# sensors.net
KiCad netlist of a schematic drawn in Altium Designer
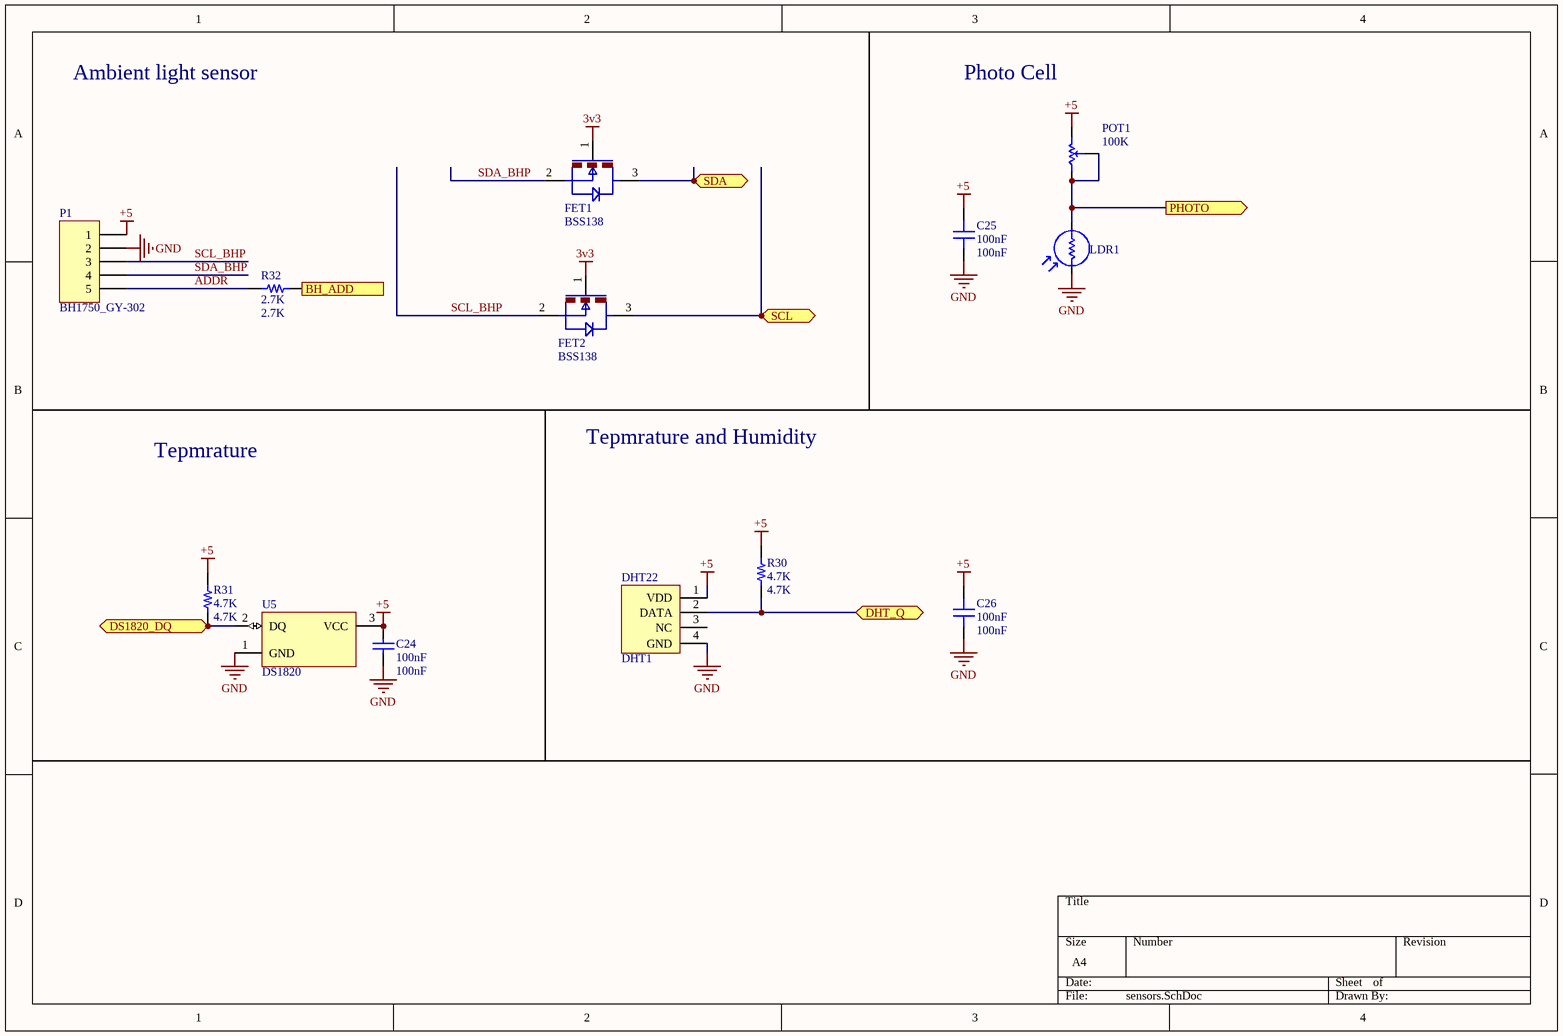
[diagram p0: sensors.SchDoc]

(export (version "E")
  (design (tool "Eeschema 10.0.6"))
  (components
    (comp (ref "C24")
      (value "100nF")
      (footprint "0603C")
      (description "CAP SMD 0603")
      (fields (field (name "ALTIUM_VALUE") "100nF") (field (name "PUBLISHER") "Altium Limited"))
      (libsource (lib "Miscellaneous Devices") (part "Cap"))
    )
    (comp (ref "C25")
      (value "100nF")
      (footprint "0603C")
      (description "CAP SMD 0603")
      (fields (field (name "PART NUMBER") "C0805X106K9RAC7800") (field (name "ALTIUM_VALUE") "100nF"))
      (libsource (lib "lamp control-ver2") (part "Capacitor"))
    )
    (comp (ref "C26")
      (value "100nF")
      (footprint "0603C")
      (description "CAP SMD 0603")
      (fields (field (name "PART NUMBER") "C0805X106K9RAC7800") (field (name "ALTIUM_VALUE") "100nF"))
      (libsource (lib "lamp control-ver2") (part "Capacitor"))
    )
    (comp (ref "DHT1")
      (value "DHT22")
      (footprint "DHT22")
      (description "Temprature & Humidity Sensor")
      (libsource (lib "Altium") (part "DHT22"))
    )
    (comp (ref "FET1")
      (value "BSS138")
      (footprint "SOT-23")
      (description "MOSFET N-channel SMD")
      (libsource (lib "ZetaBoard_Lib") (part "BSS138"))
    )
    (comp (ref "FET2")
      (value "BSS138")
      (footprint "SOT-23")
      (description "MOSFET N-channel SMD")
      (libsource (lib "ZetaBoard_Lib") (part "BSS138"))
    )
    (comp (ref "LDR1")
      (value "PhotoCell-5mm")
      (footprint "PhotoCell")
      (description "Photo Cell- Variable Resistor With Light")
      (fields (field (name "DESIGNER") "Saeid Jorablo"))
      (libsource (lib "Altium") (part "LDR"))
    )
    (comp (ref "P1")
      (value "BH1750_GY-302")
      (footprint "BH1750")
      (description "Ambiant light sensor")
      (fields (field (name "PUBLISHER") "Altium Limited"))
      (libsource (lib "Altium (2)") (part "Header 5"))
    )
    (comp (ref "POT1")
      (value "100K")
      (footprint "POT 2")
      (description "Variable Resistor")
      (libsource (lib "Altium (2)") (part "POT"))
    )
    (comp (ref "R30")
      (value "4.7K")
      (footprint "0603R")
      (description "RES SMD 0603")
      (fields (field (name "PART NUMBER") "RCS0805100KFKEA") (field (name "ALTIUM_VALUE") "4.7K"))
      (libsource (lib "lamp control-ver2") (part "Resistor"))
    )
    (comp (ref "R31")
      (value "4.7K")
      (footprint "0603R")
      (description "RES SMD 0603")
      (fields (field (name "PART NUMBER") "RCS0805100KFKEA") (field (name "ALTIUM_VALUE") "4.7K"))
      (libsource (lib "lamp control-ver2") (part "Resistor"))
    )
    (comp (ref "R32")
      (value "2.7K")
      (footprint "0603R")
      (description "RES SMD 0603")
      (fields (field (name "PART NUMBER") "RCS0805100KFKEA") (field (name "ALTIUM_VALUE") "2.7K"))
      (libsource (lib "lamp control-ver2") (part "Resistor"))
    )
    (comp (ref "U5")
      (value "DS1820")
      (footprint "DS1820")
      (description "1-Wire Digital Thermometer")
      (fields (field (name "PUBLISHER") "Altium Limited"))
      (libsource (lib "PicPars.com_usefully_Library") (part "DS1820"))
    )
  )
  (nets
    (net (code "1") (name "+5") (class "Default")
      (node (ref "C24") (pin "2") (pinfunction "2_2") (pintype "passive"))
      (node (ref "C25") (pin "1") (pinfunction "1_1") (pintype "passive"))
      (node (ref "C26") (pin "1") (pinfunction "1_1") (pintype "passive"))
      (node (ref "DHT1") (pin "1") (pinfunction "VDD_1") (pintype "passive"))
      (node (ref "P1") (pin "1") (pinfunction "1_1") (pintype "passive"))
      (node (ref "POT1") (pin "2") (pinfunction "CW_2") (pintype "passive"))
      (node (ref "R30") (pin "2") (pinfunction "2_2") (pintype "passive"))
      (node (ref "R31") (pin "2") (pinfunction "2_2") (pintype "passive"))
      (node (ref "U5") (pin "3") (pinfunction "VCC_3") (pintype "power_in"))
    )
    (net (code "2") (name "/ADDR") (class "Default")
      (node (ref "P1") (pin "5") (pinfunction "5_5") (pintype "passive"))
      (node (ref "R32") (pin "2") (pinfunction "2_2") (pintype "passive"))
    )
    (net (code "3") (name "/BH_ADD") (class "Default")
      (node (ref "R32") (pin "1") (pinfunction "1_1") (pintype "passive"))
    )
    (net (code "4") (name "/DHT_Q") (class "Default")
      (node (ref "DHT1") (pin "2") (pinfunction "DATA_2") (pintype "passive"))
      (node (ref "R30") (pin "1") (pinfunction "1_1") (pintype "passive"))
    )
    (net (code "5") (name "/DS1820_DQ") (class "Default")
      (node (ref "R31") (pin "1") (pinfunction "1_1") (pintype "passive"))
      (node (ref "U5") (pin "2") (pinfunction "DQ_2") (pintype "bidirectional"))
    )
    (net (code "6") (name "/PHOTO") (class "Default")
      (node (ref "LDR1") (pin "2") (pintype "passive"))
      (node (ref "POT1") (pin "1") (pinfunction "CCW_1") (pintype "passive"))
      (node (ref "POT1") (pin "3") (pinfunction "SetPoint_3") (pintype "passive"))
    )
    (net (code "7") (name "/SCL") (class "Default")
      (node (ref "FET2") (pin "3") (pinfunction "D_3") (pintype "passive"))
    )
    (net (code "8") (name "/SCL_BHP") (class "Default")
      (node (ref "FET2") (pin "2") (pinfunction "S_2") (pintype "passive"))
      (node (ref "P1") (pin "3") (pinfunction "3_3") (pintype "passive"))
    )
    (net (code "9") (name "/SDA") (class "Default")
      (node (ref "FET1") (pin "3") (pinfunction "D_3") (pintype "passive"))
    )
    (net (code "10") (name "/SDA_BHP") (class "Default")
      (node (ref "FET1") (pin "2") (pinfunction "S_2") (pintype "passive"))
      (node (ref "P1") (pin "4") (pinfunction "4_4") (pintype "passive"))
    )
    (net (code "11") (name "3v3") (class "Default")
      (node (ref "FET1") (pin "1") (pinfunction "G_1") (pintype "passive"))
      (node (ref "FET2") (pin "1") (pinfunction "G_1") (pintype "passive"))
    )
    (net (code "12") (name "GND") (class "Default")
      (node (ref "C24") (pin "1") (pinfunction "1_1") (pintype "passive"))
      (node (ref "C25") (pin "2") (pinfunction "2_2") (pintype "passive"))
      (node (ref "C26") (pin "2") (pinfunction "2_2") (pintype "passive"))
      (node (ref "DHT1") (pin "4") (pinfunction "GND_4") (pintype "passive"))
      (node (ref "LDR1") (pin "1") (pintype "passive"))
      (node (ref "P1") (pin "2") (pinfunction "2_2") (pintype "passive"))
      (node (ref "U5") (pin "1") (pinfunction "GND_1") (pintype "power_in"))
    )
    (net (code "13") (name "unconnected-(DHT1-NC-Pad3)") (class "Default")
      (node (ref "DHT1") (pin "3") (pinfunction "NC_3") (pintype "passive"))
    )
  )
)
